# PR9021.net
KiCad netlist of a schematic drawn in EAGLE
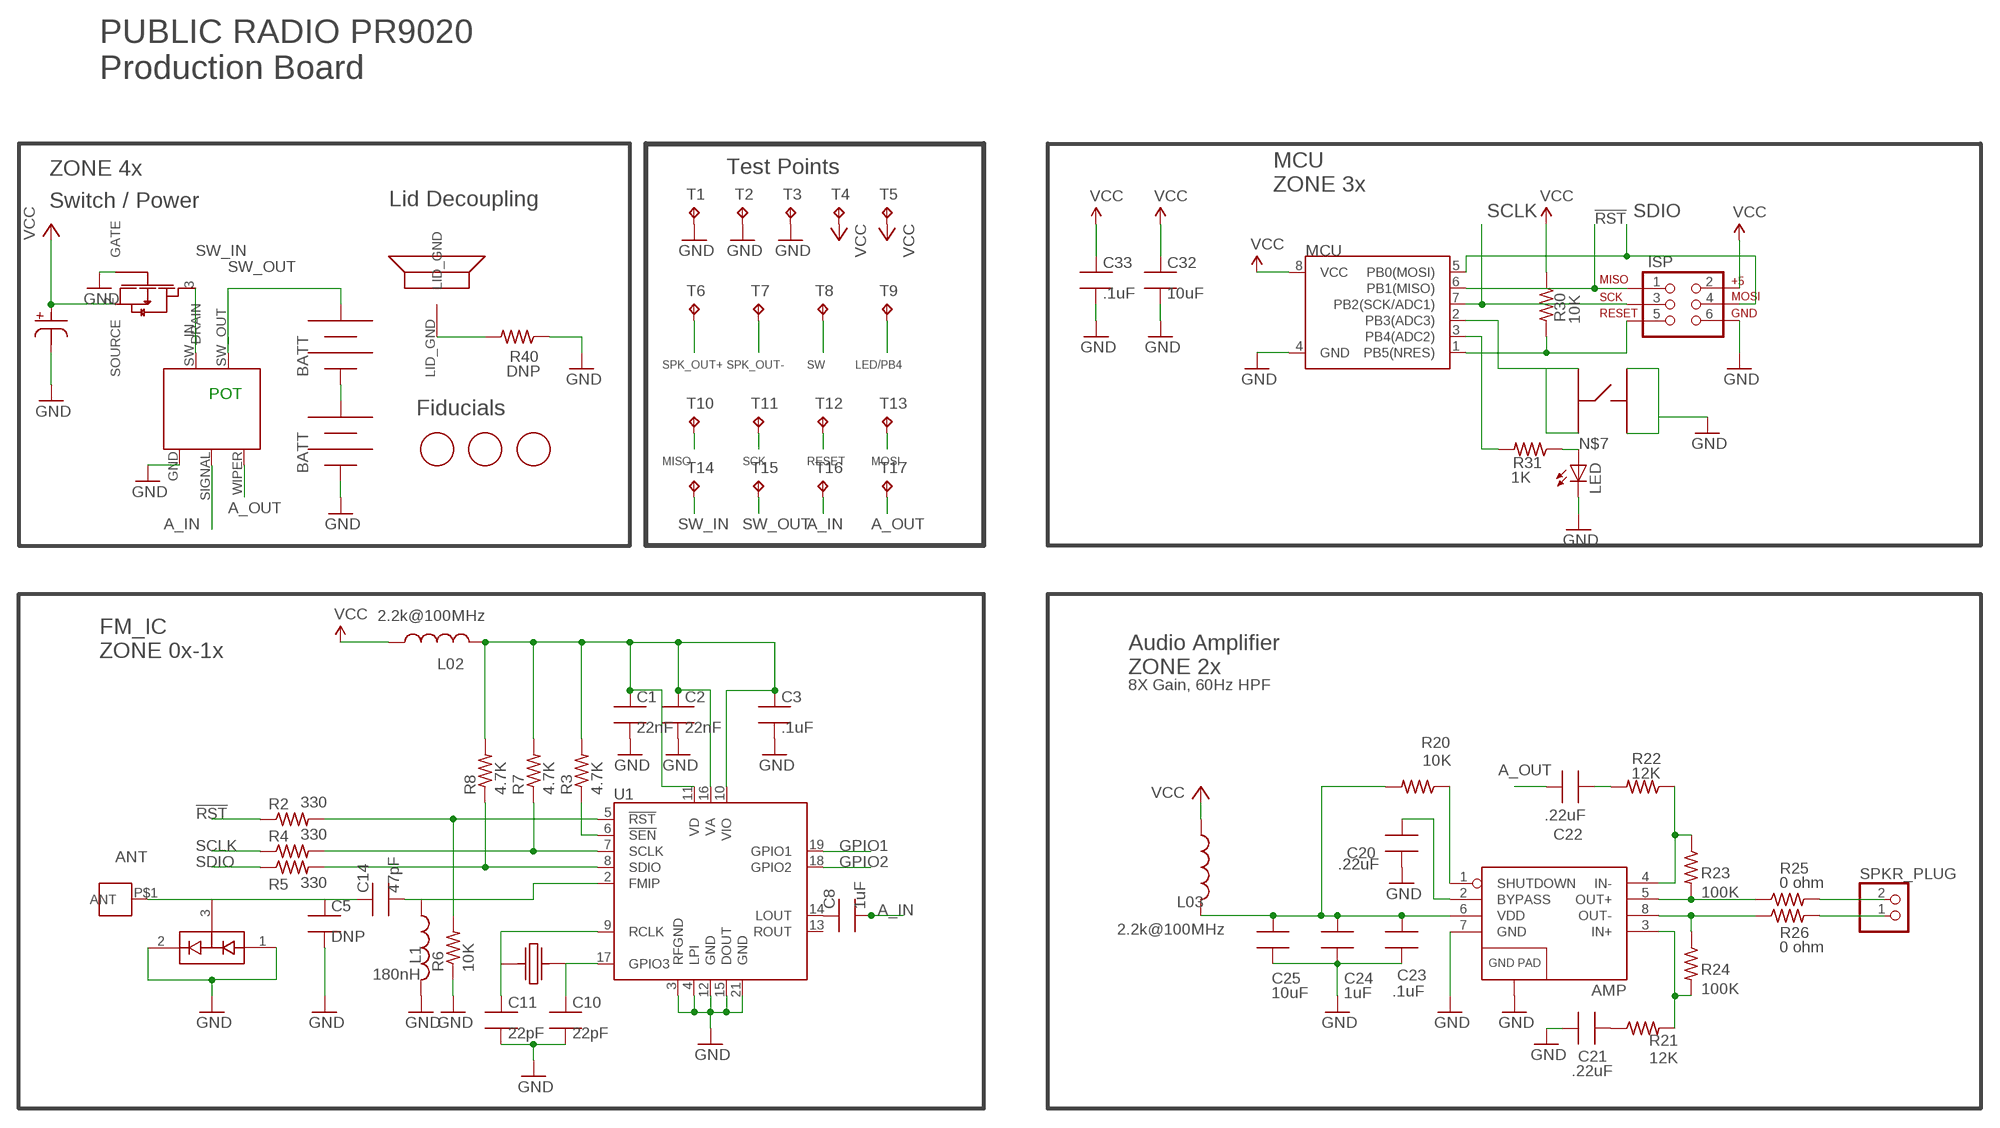
[diagram p0: schematic, sheet 1]

(export (version "E")
  (design (tool "Eeschema 10.0.6"))
  (components
    (comp (ref "AMP")
      (value "TPA6203A1")
      (footprint "eagle-import:8-MSOP")
      (libsource (lib "eagle-import") (part "TPA6203A1"))
    )
    (comp (ref "ANT_MOUNT")
      (value "DNP")
      (footprint "eagle-import:M3_BOLT_HOLE")
      (libsource (lib "eagle-import") (part "M3_SCREW_POST"))
    )
    (comp (ref "C1")
      (value "22nF")
      (footprint "eagle-import:0603_CPL")
      (fields
        (field (name "MFG_PN") "CL10B223KB8NNNC")
        (field (name "TOL") "10%")
        (field (name "VOLTAGE") "16V")
      )
      (libsource (lib "eagle-import") (part "C_SMT_0603_CPL"))
    )
    (comp (ref "C2")
      (value "22nF")
      (footprint "eagle-import:0603_CPL")
      (fields
        (field (name "MFG_PN") "CL10B223KB8NNNC")
        (field (name "TOL") "10%")
        (field (name "VOLTAGE") "16V")
      )
      (libsource (lib "eagle-import") (part "C_SMT_0603_CPL"))
    )
    (comp (ref "C3")
      (value ".1uF")
      (footprint "eagle-import:0603_CPL")
      (fields
        (field (name "MFG_PN") "CL10B104KB8SFNC")
        (field (name "TOL") "10%")
        (field (name "VOLTAGE") "16V")
      )
      (libsource (lib "eagle-import") (part "C_SMT_0603_CPL"))
    )
    (comp (ref "C5")
      (value "DNP")
      (footprint "eagle-import:0603_CPL")
      (fields (field (name "MFG_PN") "DNP") (field (name "TOL") "2%") (field (name "VOLTAGE") "50V"))
      (libsource (lib "eagle-import") (part "C_SMT_0603_CPL"))
    )
    (comp (ref "C8")
      (value "1uF")
      (footprint "eagle-import:0603_CPL")
      (fields
        (field (name "MFG_PN") "CL10B105KP8NNNC")
        (field (name "TOL") "10%")
        (field (name "VOLTAGE") "10V")
      )
      (libsource (lib "eagle-import") (part "C_SMT_0603_CPL"))
    )
    (comp (ref "C10")
      (value "22pF")
      (footprint "eagle-import:0603_CPL")
      (fields
        (field (name "MFG_PN") "C1608C0G1H220J080AA")
        (field (name "TOL") "5%")
        (field (name "VOLTAGE") "50V")
      )
      (libsource (lib "eagle-import") (part "C_SMT_0603_CPL"))
    )
    (comp (ref "C11")
      (value "22pF")
      (footprint "eagle-import:0603_CPL")
      (fields
        (field (name "MFG_PN") "C1608C0G1H220J080AA")
        (field (name "TOL") "5%")
        (field (name "VOLTAGE") "50V")
      )
      (libsource (lib "eagle-import") (part "C_SMT_0603_CPL"))
    )
    (comp (ref "C14")
      (value "47pF")
      (footprint "eagle-import:0603_CPL")
      (fields
        (field (name "MFG_PN") "CL10C470JB8NCNC")
        (field (name "TOL") "5%")
        (field (name "VOLTAGE") "50V")
      )
      (libsource (lib "eagle-import") (part "C_SMT_0603_CPL"))
    )
    (comp (ref "C20")
      (value ".22uF")
      (footprint "eagle-import:0603_CPL")
      (fields
        (field (name "MFG_PN") "C1608X7R1C224K080AC")
        (field (name "TOL") "10%")
        (field (name "VOLTAGE") "16V")
      )
      (libsource (lib "eagle-import") (part "C_SMT_0603_CPL"))
    )
    (comp (ref "C21")
      (value ".22uF")
      (footprint "eagle-import:0603_CPL")
      (fields
        (field (name "MFG_PN") "C1608X7R1C224K080AC")
        (field (name "TOL") "10%")
        (field (name "VOLTAGE") "16V")
      )
      (libsource (lib "eagle-import") (part "C_SMT_0603_CPL"))
    )
    (comp (ref "C22")
      (value ".22uF")
      (footprint "eagle-import:0603_CPL")
      (fields
        (field (name "MFG_PN") "C1608X7R1C224K080AC")
        (field (name "TOL") "10%")
        (field (name "VOLTAGE") "16V")
      )
      (libsource (lib "eagle-import") (part "C_SMT_0603_CPL"))
    )
    (comp (ref "C23")
      (value ".1uF")
      (footprint "eagle-import:0603_CPL")
      (fields
        (field (name "MFG_PN") "CL10B104KB8SFNC")
        (field (name "TOL") "10%")
        (field (name "VOLTAGE") "16V")
      )
      (libsource (lib "eagle-import") (part "C_SMT_0603_CPL"))
    )
    (comp (ref "C24")
      (value "1uF")
      (footprint "eagle-import:0603_CPL")
      (fields
        (field (name "MFG_PN") "CL10B105KP8NNNC")
        (field (name "TOL") "10%")
        (field (name "VOLTAGE") "10V")
      )
      (libsource (lib "eagle-import") (part "C_SMT_0603_CPL"))
    )
    (comp (ref "C25")
      (value "10uF")
      (footprint "eagle-import:0603_CPL")
      (fields
        (field (name "MFG_PN") "CL10A106MQ8NNNC")
        (field (name "TOL") "20%")
        (field (name "VOLTAGE") "6.3V")
      )
      (libsource (lib "eagle-import") (part "C_SMT_0603_CPL"))
    )
    (comp (ref "C32")
      (value "10uF")
      (footprint "eagle-import:0603_CPL")
      (fields
        (field (name "MFG_PN") "CL10A106MQ8NNNC")
        (field (name "TOL") "20%")
        (field (name "VOLTAGE") "6.3V")
      )
      (libsource (lib "eagle-import") (part "C_SMT_0603_CPL"))
    )
    (comp (ref "C33")
      (value ".1uF")
      (footprint "eagle-import:0603_CPL")
      (fields
        (field (name "MFG_PN") "CL10B104KB8SFNC")
        (field (name "TOL") "10%")
        (field (name "VOLTAGE") "16V")
      )
      (libsource (lib "eagle-import") (part "C_SMT_0603_CPL"))
    )
    (comp (ref "C40")
      (value "220uF")
      (footprint "eagle-import:NICHICON_UD_63")
      (fields (field (name "TOL") "20%") (field (name "VOLTAGE") "16V"))
      (libsource (lib "eagle-import") (part "NICHICON_SERIESUD"))
    )
    (comp (ref "D1")
      (value "BAV99")
      (footprint "eagle-import:SOT23_CPL")
      (fields (field (name "MFG_PN") "BAV99,215"))
      (libsource (lib "eagle-import") (part "BAV99"))
    )
    (comp (ref "FET1")
      (value "AO3435")
      (footprint "eagle-import:SOT23_CPL")
      (fields (field (name "MFG_PN") "AO3435"))
      (libsource (lib "eagle-import") (part "AO3435"))
    )
    (comp (ref "ISP")
      (value "AVR_SPI_PRG_6NS")
      (footprint "eagle-import:2X3-NS")
      (libsource (lib "eagle-import") (part "AVR_SPI_PRG_6NS"))
    )
    (comp (ref "JP5")
      (value "BK-92_MPD_AA_BATT_CLIP")
      (footprint "eagle-import:BK92_AA_BATT")
      (fields (field (name "MFG_PN") "2 of BK92 - supplied by CL Labs"))
      (libsource (lib "eagle-import") (part "BK-92_MPD_AA_BATT_CLIP"))
    )
    (comp (ref "JP6")
      (value "BK-92_MPD_AA_BATT_CLIP")
      (footprint "eagle-import:BK92_AA_BATT")
      (fields (field (name "MFG_PN") "2 of BK92 - supplied by CL Labs"))
      (libsource (lib "eagle-import") (part "BK-92_MPD_AA_BATT_CLIP"))
    )
    (comp (ref "L1")
      (value "180nH")
      (footprint "eagle-import:0805_ADAFRUIT")
      (fields
        (field (name "CURRENT") "400mA")
        (field (name "DCR") "640m")
        (field (name "MFG_PN") "AISC-0805-R18J-T")
        (field (name "TOL") "5%")
      )
      (libsource (lib "eagle-import") (part "L_SMT_0805_ADAFRUIT"))
    )
    (comp (ref "L02")
      (value "2.2k@100MHz")
      (footprint "eagle-import:0603_CPL")
      (fields
        (field (name "CURRENT") "150mA")
        (field (name "DCR") "2.3")
        (field (name "MFG_PN") "HZ0603A222R-10")
      )
      (libsource (lib "eagle-import") (part "L_SMT_0603_CPL"))
    )
    (comp (ref "L03")
      (value "2.2k@100MHz")
      (footprint "eagle-import:0603_CPL")
      (fields
        (field (name "CURRENT") "150mA")
        (field (name "DCR") "2.3")
        (field (name "MFG_PN") "HZ0603A222R-10")
      )
      (libsource (lib "eagle-import") (part "L_SMT_0603_CPL"))
    )
    (comp (ref "LED")
      (value "LEDCHIPLED_0805")
      (footprint "eagle-import:CHIPLED_0805")
      (libsource (lib "eagle-import") (part "LEDCHIPLED_0805"))
    )
    (comp (ref "MARK1")
      (value "FIDUCIAL")
      (footprint "eagle-import:FIDUCIAL_1MM")
      (libsource (lib "eagle-import") (part "FIDUCIAL"))
    )
    (comp (ref "MARK2")
      (value "FIDUCIAL")
      (footprint "eagle-import:FIDUCIAL_1MM")
      (libsource (lib "eagle-import") (part "FIDUCIAL"))
    )
    (comp (ref "MARK3")
      (value "FIDUCIAL")
      (footprint "eagle-import:FIDUCIAL_1MM")
      (libsource (lib "eagle-import") (part "FIDUCIAL"))
    )
    (comp (ref "MCU")
      (value "ATTINY45TINY45-20-SMT")
      (footprint "eagle-import:8-SOIC")
      (libsource (lib "eagle-import") (part "ATTINY45TINY45-20-SMT"))
    )
    (comp (ref "R1")
      (value "RV170SF_TAIWANA_POT_SW")
      (footprint "eagle-import:RV170SF_SW_POT")
      (fields (field (name "MFG_PN") "RV170SF-43-20F-A10K - supplied by CL Labs"))
      (libsource (lib "eagle-import") (part "RV170SF_TAIWANA_POT_SW"))
    )
    (comp (ref "R2")
      (value "330")
      (footprint "eagle-import:0603_CPL")
      (fields (field (name "MFG_PN") "MCR03ERTJ331") (field (name "POWER") "1/10W") (field (name "TOL") "5%"))
      (libsource (lib "eagle-import") (part "R_SMT_R0603_CPL"))
    )
    (comp (ref "R3")
      (value "4.7K")
      (footprint "eagle-import:0603_CPL")
      (fields
        (field (name "MFG_PN") "ERJ-3EKF4701V")
        (field (name "POWER") "1/10W")
        (field (name "TOL") "1%")
      )
      (libsource (lib "eagle-import") (part "R_SMT_R0603_CPL"))
    )
    (comp (ref "R4")
      (value "330")
      (footprint "eagle-import:0603_CPL")
      (fields (field (name "MFG_PN") "MCR03ERTJ331") (field (name "POWER") "1/10W") (field (name "TOL") "5%"))
      (libsource (lib "eagle-import") (part "R_SMT_R0603_CPL"))
    )
    (comp (ref "R5")
      (value "330")
      (footprint "eagle-import:0603_CPL")
      (fields (field (name "MFG_PN") "MCR03ERTJ331") (field (name "POWER") "1/10W") (field (name "TOL") "5%"))
      (libsource (lib "eagle-import") (part "R_SMT_R0603_CPL"))
    )
    (comp (ref "R6")
      (value "10K")
      (footprint "eagle-import:0603_CPL")
      (fields
        (field (name "MFG_PN") "ERJ-3GEYJ103V")
        (field (name "POWER") "1/10W")
        (field (name "TOL") "5%")
      )
      (libsource (lib "eagle-import") (part "R_SMT_R0603_CPL"))
    )
    (comp (ref "R7")
      (value "4.7K")
      (footprint "eagle-import:0603_CPL")
      (fields
        (field (name "MFG_PN") "ERJ-3EKF4701V")
        (field (name "POWER") "1/10W")
        (field (name "TOL") "1%")
      )
      (libsource (lib "eagle-import") (part "R_SMT_R0603_CPL"))
    )
    (comp (ref "R8")
      (value "4.7K")
      (footprint "eagle-import:0603_CPL")
      (fields
        (field (name "MFG_PN") "ERJ-3EKF4701V")
        (field (name "POWER") "1/10W")
        (field (name "TOL") "1%")
      )
      (libsource (lib "eagle-import") (part "R_SMT_R0603_CPL"))
    )
    (comp (ref "R20")
      (value "10K")
      (footprint "eagle-import:0603_CPL")
      (fields
        (field (name "MFG_PN") "ERJ-3GEYJ103V")
        (field (name "POWER") "1/10W")
        (field (name "TOL") "5%")
      )
      (libsource (lib "eagle-import") (part "R_SMT_R0603_CPL"))
    )
    (comp (ref "R21")
      (value "12K")
      (footprint "eagle-import:0603_CPL")
      (fields
        (field (name "MFG_PN") "RC0603FR-0712KL")
        (field (name "POWER") "1/10W")
        (field (name "TOL") "1%")
      )
      (libsource (lib "eagle-import") (part "R_SMT_R0603_CPL"))
    )
    (comp (ref "R22")
      (value "12K")
      (footprint "eagle-import:0603_CPL")
      (fields
        (field (name "MFG_PN") "RC0603FR-0712KL")
        (field (name "POWER") "1/10W")
        (field (name "TOL") "1%")
      )
      (libsource (lib "eagle-import") (part "R_SMT_R0603_CPL"))
    )
    (comp (ref "R23")
      (value "100K")
      (footprint "eagle-import:0603_CPL")
      (fields
        (field (name "MFG_PN") "ERJ-3EKF1003V")
        (field (name "POWER") "1/10W")
        (field (name "TOL") "1%")
      )
      (libsource (lib "eagle-import") (part "R_SMT_R0603_CPL"))
    )
    (comp (ref "R24")
      (value "100K")
      (footprint "eagle-import:0603_CPL")
      (fields
        (field (name "MFG_PN") "ERJ-3EKF1003V")
        (field (name "POWER") "1/10W")
        (field (name "TOL") "1%")
      )
      (libsource (lib "eagle-import") (part "R_SMT_R0603_CPL"))
    )
    (comp (ref "R25")
      (value "0 ohm")
      (footprint "eagle-import:0805_ADAFRUIT")
      (fields (field (name "MFG_PN") "ERJ-6GEY0R00V"))
      (libsource (lib "eagle-import") (part "R_SMT_0805_ADAFRUIT"))
    )
    (comp (ref "R26")
      (value "0 ohm")
      (footprint "eagle-import:0805_ADAFRUIT")
      (fields (field (name "MFG_PN") "ERJ-6GEY0R00V"))
      (libsource (lib "eagle-import") (part "R_SMT_0805_ADAFRUIT"))
    )
    (comp (ref "R30")
      (value "10K")
      (footprint "eagle-import:0603_CPL")
      (fields
        (field (name "MFG_PN") "ERJ-3GEYJ103V")
        (field (name "POWER") "1/10W")
        (field (name "TOL") "5%")
      )
      (libsource (lib "eagle-import") (part "R_SMT_R0603_CPL"))
    )
    (comp (ref "R31")
      (value "1K")
      (footprint "eagle-import:0603_CPL")
      (fields
        (field (name "MFG_PN") "ERJ-3EKF1001V")
        (field (name "POWER") "1/10W")
        (field (name "TOL") "1%")
      )
      (libsource (lib "eagle-import") (part "R_SMT_R0603_CPL"))
    )
    (comp (ref "R40")
      (value "DNP")
      (footprint "eagle-import:0603_CPL")
      (fields (field (name "MFG_PN") "ERJ-3GEY0R00V"))
      (libsource (lib "eagle-import") (part "R_SMT_R0603_CPL"))
    )
    (comp (ref "SPKR_PLACE")
      (value "DNP")
      (footprint "eagle-import:PR2023_SPKR_PLACE")
      (libsource (lib "eagle-import") (part "PR2023_SPKR"))
    )
    (comp (ref "SPKR_PLUG")
      (value "JST_2PIN-SMT-RA")
      (footprint "eagle-import:JST-B2B-PH-SM4-TB")
      (libsource (lib "eagle-import") (part "JST_2PIN-SMT-RA"))
    )
    (comp (ref "SW1")
      (value "C&K_PTS645")
      (footprint "eagle-import:C&K_PTS645_SMT")
      (libsource (lib "eagle-import") (part "C&K_PTS645"))
    )
    (comp (ref "T1")
      (value "TPTP20R")
      (footprint "eagle-import:TP20R")
      (libsource (lib "eagle-import") (part "TPTP20R"))
    )
    (comp (ref "T2")
      (value "TPTP20R")
      (footprint "eagle-import:TP20R")
      (libsource (lib "eagle-import") (part "TPTP20R"))
    )
    (comp (ref "T3")
      (value "TPTP20R")
      (footprint "eagle-import:TP20R")
      (libsource (lib "eagle-import") (part "TPTP20R"))
    )
    (comp (ref "T4")
      (value "TPTP20R")
      (footprint "eagle-import:TP20R")
      (libsource (lib "eagle-import") (part "TPTP20R"))
    )
    (comp (ref "T5")
      (value "TPTP20R")
      (footprint "eagle-import:TP20R")
      (libsource (lib "eagle-import") (part "TPTP20R"))
    )
    (comp (ref "T6")
      (value "TPTP20R")
      (footprint "eagle-import:TP20R")
      (libsource (lib "eagle-import") (part "TPTP20R"))
    )
    (comp (ref "T7")
      (value "TPTP20R")
      (footprint "eagle-import:TP20R")
      (libsource (lib "eagle-import") (part "TPTP20R"))
    )
    (comp (ref "T8")
      (value "TPTP20R")
      (footprint "eagle-import:TP20R")
      (libsource (lib "eagle-import") (part "TPTP20R"))
    )
    (comp (ref "T9")
      (value "TPTP20R")
      (footprint "eagle-import:TP20R")
      (libsource (lib "eagle-import") (part "TPTP20R"))
    )
    (comp (ref "T10")
      (value "TPTP20R")
      (footprint "eagle-import:TP20R")
      (libsource (lib "eagle-import") (part "TPTP20R"))
    )
    (comp (ref "T11")
      (value "TPTP20R")
      (footprint "eagle-import:TP20R")
      (libsource (lib "eagle-import") (part "TPTP20R"))
    )
    (comp (ref "T12")
      (value "TPTP20R")
      (footprint "eagle-import:TP20R")
      (libsource (lib "eagle-import") (part "TPTP20R"))
    )
    (comp (ref "T13")
      (value "TPTP20R")
      (footprint "eagle-import:TP20R")
      (libsource (lib "eagle-import") (part "TPTP20R"))
    )
    (comp (ref "T14")
      (value "TPTP20R")
      (footprint "eagle-import:TP20R")
      (libsource (lib "eagle-import") (part "TPTP20R"))
    )
    (comp (ref "T15")
      (value "TPTP20R")
      (footprint "eagle-import:TP20R")
      (libsource (lib "eagle-import") (part "TPTP20R"))
    )
    (comp (ref "T16")
      (value "TPTP20R")
      (footprint "eagle-import:TP20R")
      (libsource (lib "eagle-import") (part "TPTP20R"))
    )
    (comp (ref "T17")
      (value "TPTP20R")
      (footprint "eagle-import:TP20R")
      (libsource (lib "eagle-import") (part "TPTP20R"))
    )
    (comp (ref "U1")
      (value "SI4702-C19-GMR")
      (footprint "eagle-import:SI470X_20_QFN")
      (fields (field (name "MFG_PN") "Si4702 C19 GM - supplied by CL Labs"))
      (libsource (lib "eagle-import") (part "SI4702-C19-GMR"))
    )
    (comp (ref "X1")
      (value "ABS25XTAL")
      (footprint "eagle-import:4-SOJ")
      (libsource (lib "eagle-import") (part "ABS25XTAL"))
    )
  )
  (nets
    (net (code "1") (name "/ANT") (class "Default")
      (node (ref "ANT_MOUNT") (pin "P$1") (pinfunction "ANT_P$1") (pintype "bidirectional"))
      (node (ref "C14") (pin "1") (pinfunction "1_1") (pintype "passive"))
      (node (ref "C5") (pin "1") (pinfunction "1_1") (pintype "passive"))
      (node (ref "D1") (pin "3") (pinfunction "COM_3") (pintype "bidirectional"))
    )
    (net (code "2") (name "/A_IN") (class "Default")
      (node (ref "C8") (pin "2") (pinfunction "2_2") (pintype "passive"))
      (node (ref "R1") (pin "SIGNAL") (pinfunction "SIGNAL_SIGNAL") (pintype "bidirectional"))
      (node (ref "T16") (pin "TP") (pinfunction "TP_TP") (pintype "input"))
    )
    (net (code "3") (name "/A_OUT") (class "Default")
      (node (ref "C22") (pin "2") (pinfunction "2_2") (pintype "passive"))
      (node (ref "R1") (pin "WIPER") (pinfunction "WIPER_WIPER") (pintype "bidirectional"))
      (node (ref "T17") (pin "TP") (pinfunction "TP_TP") (pintype "input"))
    )
    (net (code "4") (name "/GPIO1") (class "Default")
      (node (ref "U1") (pin "19") (pinfunction "GPIO1_19") (pintype "bidirectional"))
    )
    (net (code "5") (name "/GPIO2") (class "Default")
      (node (ref "U1") (pin "18") (pinfunction "GPIO2_18") (pintype "bidirectional"))
    )
    (net (code "6") (name "/LED{slash}PB4") (class "Default")
      (node (ref "MCU") (pin "3") (pinfunction "PB4(ADC2)_3") (pintype "bidirectional"))
      (node (ref "R31") (pin "2") (pinfunction "2_2") (pintype "passive"))
      (node (ref "T9") (pin "TP") (pinfunction "TP_TP") (pintype "input"))
    )
    (net (code "7") (name "/N$7") (class "Default")
      (node (ref "LED") (pin "A") (pinfunction "A_A") (pintype "passive"))
      (node (ref "R31") (pin "1") (pinfunction "1_1") (pintype "passive"))
    )
    (net (code "8") (name "/RESET") (class "Default")
      (node (ref "ISP") (pin "5") (pinfunction "5_5") (pintype "passive"))
      (node (ref "MCU") (pin "1") (pinfunction "PB5(NRES)_1") (pintype "bidirectional"))
      (node (ref "R30") (pin "2") (pinfunction "2_2") (pintype "passive"))
      (node (ref "T12") (pin "TP") (pinfunction "TP_TP") (pintype "input"))
    )
    (net (code "9") (name "/SCLK") (class "Default")
      (node (ref "ISP") (pin "3") (pinfunction "3_3") (pintype "passive"))
      (node (ref "MCU") (pin "7") (pinfunction "PB2(SCK/ADC1)_7") (pintype "bidirectional"))
      (node (ref "R4") (pin "1") (pinfunction "1_1") (pintype "passive"))
      (node (ref "T11") (pin "TP") (pinfunction "TP_TP") (pintype "input"))
    )
    (net (code "10") (name "/SDIO") (class "Default")
      (node (ref "ISP") (pin "4") (pinfunction "4_4") (pintype "passive"))
      (node (ref "MCU") (pin "5") (pinfunction "PB0(MOSI)_5") (pintype "bidirectional"))
      (node (ref "R5") (pin "1") (pinfunction "1_1") (pintype "passive"))
      (node (ref "T13") (pin "TP") (pinfunction "TP_TP") (pintype "input"))
    )
    (net (code "11") (name "/SPK_OUT+") (class "Default")
      (node (ref "R25") (pin "2") (pinfunction "2_2") (pintype "passive"))
      (node (ref "SPKR_PLUG") (pin "2") (pinfunction "1_2") (pintype "passive"))
      (node (ref "T6") (pin "TP") (pinfunction "TP_TP") (pintype "input"))
    )
    (net (code "12") (name "/SPK_OUT-") (class "Default")
      (node (ref "R26") (pin "2") (pinfunction "2_2") (pintype "passive"))
      (node (ref "SPKR_PLUG") (pin "1") (pinfunction "2_1") (pintype "passive"))
      (node (ref "T7") (pin "TP") (pinfunction "TP_TP") (pintype "input"))
    )
    (net (code "13") (name "/SW") (class "Default")
      (node (ref "MCU") (pin "2") (pinfunction "PB3(ADC3)_2") (pintype "bidirectional"))
      (node (ref "SW1") (pin "P$3") (pinfunction "P$3_P$3") (pintype "bidirectional"))
      (node (ref "SW1") (pin "P$4") (pinfunction "P$4_P$4") (pintype "bidirectional"))
      (node (ref "T8") (pin "TP") (pinfunction "TP_TP") (pintype "input"))
    )
    (net (code "14") (name "/SW_IN") (class "Default")
      (node (ref "FET1") (pin "3") (pinfunction "DRAIN_3") (pintype "bidirectional"))
      (node (ref "R1") (pin "SW_IN") (pinfunction "SW_IN_SW_IN") (pintype "bidirectional"))
      (node (ref "T14") (pin "TP") (pinfunction "TP_TP") (pintype "input"))
    )
    (net (code "15") (name "/SW_OUT") (class "Default")
      (node (ref "JP5") (pin "POS") (pinfunction "POS_POS") (pintype "bidirectional"))
      (node (ref "JP5") (pin "POS@2") (pinfunction "POS_POS@2") (pintype "bidirectional"))
      (node (ref "R1") (pin "SW_OUT") (pinfunction "SW_OUT_SW_OUT") (pintype "bidirectional"))
      (node (ref "T15") (pin "TP") (pinfunction "TP_TP") (pintype "input"))
    )
    (net (code "16") (name "/~{RST}") (class "Default")
      (node (ref "ISP") (pin "1") (pinfunction "1_1") (pintype "passive"))
      (node (ref "MCU") (pin "6") (pinfunction "PB1(MISO)_6") (pintype "bidirectional"))
      (node (ref "R2") (pin "1") (pinfunction "1_1") (pintype "passive"))
      (node (ref "T10") (pin "TP") (pinfunction "TP_TP") (pintype "input"))
    )
    (net (code "17") (name "GND") (class "Default")
      (node (ref "AMP") (pin "7") (pinfunction "GND_7") (pintype "power_in"))
      (node (ref "AMP") (pin "9") (pinfunction "GND_9") (pintype "power_in"))
      (node (ref "C1") (pin "2") (pinfunction "2_2") (pintype "passive"))
      (node (ref "C10") (pin "2") (pinfunction "2_2") (pintype "passive"))
      (node (ref "C11") (pin "2") (pinfunction "2_2") (pintype "passive"))
      (node (ref "C2") (pin "2") (pinfunction "2_2") (pintype "passive"))
      (node (ref "C20") (pin "1") (pinfunction "1_1") (pintype "passive"))
      (node (ref "C21") (pin "1") (pinfunction "1_1") (pintype "passive"))
      (node (ref "C23") (pin "2") (pinfunction "2_2") (pintype "passive"))
      (node (ref "C24") (pin "2") (pinfunction "2_2") (pintype "passive"))
      (node (ref "C25") (pin "2") (pinfunction "2_2") (pintype "passive"))
      (node (ref "C3") (pin "2") (pinfunction "2_2") (pintype "passive"))
      (node (ref "C32") (pin "2") (pinfunction "2_2") (pintype "passive"))
      (node (ref "C33") (pin "2") (pinfunction "2_2") (pintype "passive"))
      (node (ref "C40") (pin "P$2") (pinfunction "P$2_P$2") (pintype "bidirectional"))
      (node (ref "C5") (pin "2") (pinfunction "2_2") (pintype "passive"))
      (node (ref "D1") (pin "1") (pinfunction "A1_1") (pintype "bidirectional"))
      (node (ref "D1") (pin "2") (pinfunction "C2_2") (pintype "bidirectional"))
      (node (ref "FET1") (pin "1") (pinfunction "GATE_1") (pintype "bidirectional"))
      (node (ref "ISP") (pin "6") (pinfunction "6_6") (pintype "passive"))
      (node (ref "JP6") (pin "NEG") (pinfunction "NEG_NEG") (pintype "bidirectional"))
      (node (ref "JP6") (pin "NEG@2") (pinfunction "NEG_NEG@2") (pintype "bidirectional"))
      (node (ref "L1") (pin "2") (pinfunction "2_2") (pintype "passive"))
      (node (ref "LED") (pin "C") (pinfunction "C_C") (pintype "passive"))
      (node (ref "MCU") (pin "4") (pinfunction "GND_4") (pintype "bidirectional"))
      (node (ref "R1") (pin "GND") (pinfunction "GND_GND") (pintype "bidirectional"))
      (node (ref "R40") (pin "1") (pinfunction "1_1") (pintype "passive"))
      (node (ref "R6") (pin "1") (pinfunction "1_1") (pintype "passive"))
      (node (ref "SW1") (pin "P$1") (pinfunction "P$1_P$1") (pintype "bidirectional"))
      (node (ref "SW1") (pin "P$2") (pinfunction "P$2_P$2") (pintype "bidirectional"))
      (node (ref "T1") (pin "TP") (pinfunction "TP_TP") (pintype "input"))
      (node (ref "T2") (pin "TP") (pinfunction "TP_TP") (pintype "input"))
      (node (ref "T3") (pin "TP") (pinfunction "TP_TP") (pintype "input"))
      (node (ref "U1") (pin "12") (pinfunction "GND_12") (pintype "bidirectional"))
      (node (ref "U1") (pin "15") (pinfunction "DOUT_15") (pintype "bidirectional"))
      (node (ref "U1") (pin "21") (pinfunction "GND_21") (pintype "bidirectional"))
      (node (ref "U1") (pin "3") (pinfunction "RFGND_3") (pintype "bidirectional"))
      (node (ref "U1") (pin "4") (pinfunction "LPI_4") (pintype "bidirectional"))
    )
    (net (code "18") (name "Net-(AMP-BYPASS)") (class "Default")
      (node (ref "AMP") (pin "2") (pinfunction "BYPASS_2") (pintype "bidirectional"))
      (node (ref "C20") (pin "2") (pinfunction "2_2") (pintype "passive"))
    )
    (net (code "19") (name "Net-(AMP-IN+)") (class "Default")
      (node (ref "AMP") (pin "3") (pinfunction "IN+_3") (pintype "bidirectional"))
      (node (ref "R21") (pin "2") (pinfunction "2_2") (pintype "passive"))
      (node (ref "R24") (pin "2") (pinfunction "2_2") (pintype "passive"))
    )
    (net (code "20") (name "Net-(AMP-IN-)") (class "Default")
      (node (ref "AMP") (pin "4") (pinfunction "IN-_4") (pintype "bidirectional"))
      (node (ref "R22") (pin "1") (pinfunction "1_1") (pintype "passive"))
      (node (ref "R23") (pin "1") (pinfunction "1_1") (pintype "passive"))
    )
    (net (code "21") (name "Net-(AMP-OUT+)") (class "Default")
      (node (ref "AMP") (pin "5") (pinfunction "OUT+_5") (pintype "bidirectional"))
      (node (ref "R23") (pin "2") (pinfunction "2_2") (pintype "passive"))
      (node (ref "R25") (pin "1") (pinfunction "1_1") (pintype "passive"))
    )
    (net (code "22") (name "Net-(AMP-OUT-)") (class "Default")
      (node (ref "AMP") (pin "8") (pinfunction "OUT-_8") (pintype "bidirectional"))
      (node (ref "R24") (pin "1") (pinfunction "1_1") (pintype "passive"))
      (node (ref "R26") (pin "1") (pinfunction "1_1") (pintype "passive"))
    )
    (net (code "23") (name "Net-(AMP-SHUTDOWN)") (class "Default")
      (node (ref "AMP") (pin "1") (pinfunction "SHUTDOWN_1") (pintype "input"))
      (node (ref "R20") (pin "1") (pinfunction "1_1") (pintype "passive"))
    )
    (net (code "24") (name "Net-(AMP-VDD)") (class "Default")
      (node (ref "AMP") (pin "6") (pinfunction "VDD_6") (pintype "power_in"))
      (node (ref "C23") (pin "1") (pinfunction "1_1") (pintype "passive"))
      (node (ref "C24") (pin "1") (pinfunction "1_1") (pintype "passive"))
      (node (ref "C25") (pin "1") (pinfunction "1_1") (pintype "passive"))
      (node (ref "L03") (pin "2") (pinfunction "2_2") (pintype "passive"))
      (node (ref "R20") (pin "2") (pinfunction "2_2") (pintype "passive"))
    )
    (net (code "25") (name "Net-(C21-Pad2)") (class "Default")
      (node (ref "C21") (pin "2") (pinfunction "2_2") (pintype "passive"))
      (node (ref "R21") (pin "1") (pinfunction "1_1") (pintype "passive"))
    )
    (net (code "26") (name "Net-(C22-Pad1)") (class "Default")
      (node (ref "C22") (pin "1") (pinfunction "1_1") (pintype "passive"))
      (node (ref "R22") (pin "2") (pinfunction "2_2") (pintype "passive"))
    )
    (net (code "27") (name "Net-(JP5-NEG-PadNEG@2)") (class "Default")
      (node (ref "JP5") (pin "NEG") (pinfunction "NEG_NEG") (pintype "bidirectional"))
      (node (ref "JP5") (pin "NEG@2") (pinfunction "NEG_NEG@2") (pintype "bidirectional"))
      (node (ref "JP6") (pin "POS") (pinfunction "POS_POS") (pintype "bidirectional"))
      (node (ref "JP6") (pin "POS@2") (pinfunction "POS_POS@2") (pintype "bidirectional"))
    )
    (net (code "28") (name "Net-(R40-Pad2)") (class "Default")
      (node (ref "R40") (pin "2") (pinfunction "2_2") (pintype "passive"))
      (node (ref "SPKR_PLACE") (pin "LID_GND") (pinfunction "LID_GND_LID_GND") (pintype "bidirectional"))
    )
    (net (code "29") (name "Net-(U1-FMIP)") (class "Default")
      (node (ref "C14") (pin "2") (pinfunction "2_2") (pintype "passive"))
      (node (ref "L1") (pin "1") (pinfunction "1_1") (pintype "passive"))
      (node (ref "U1") (pin "2") (pinfunction "FMIP_2") (pintype "bidirectional"))
    )
    (net (code "30") (name "Net-(U1-GPIO3)") (class "Default")
      (node (ref "C10") (pin "1") (pinfunction "1_1") (pintype "passive"))
      (node (ref "U1") (pin "17") (pinfunction "GPIO3_17") (pintype "bidirectional"))
      (node (ref "X1") (pin "P$4") (pinfunction "P$4_P$4") (pintype "bidirectional"))
    )
    (net (code "31") (name "Net-(U1-LOUT)") (class "Default")
      (node (ref "C8") (pin "1") (pinfunction "1_1") (pintype "passive"))
      (node (ref "U1") (pin "14") (pinfunction "LOUT_14") (pintype "bidirectional"))
    )
    (net (code "32") (name "Net-(U1-RCLK)") (class "Default")
      (node (ref "C11") (pin "1") (pinfunction "1_1") (pintype "passive"))
      (node (ref "U1") (pin "9") (pinfunction "RCLK_9") (pintype "bidirectional"))
      (node (ref "X1") (pin "P$1") (pinfunction "P$1_P$1") (pintype "bidirectional"))
    )
    (net (code "33") (name "Net-(U1-SCLK)") (class "Default")
      (node (ref "R4") (pin "2") (pinfunction "2_2") (pintype "passive"))
      (node (ref "R7") (pin "1") (pinfunction "1_1") (pintype "passive"))
      (node (ref "U1") (pin "7") (pinfunction "SCLK_7") (pintype "bidirectional"))
    )
    (net (code "34") (name "Net-(U1-SDIO)") (class "Default")
      (node (ref "R5") (pin "2") (pinfunction "2_2") (pintype "passive"))
      (node (ref "R8") (pin "1") (pinfunction "1_1") (pintype "passive"))
      (node (ref "U1") (pin "8") (pinfunction "SDIO_8") (pintype "bidirectional"))
    )
    (net (code "35") (name "Net-(U1-VA)") (class "Default")
      (node (ref "C1") (pin "1") (pinfunction "1_1") (pintype "passive"))
      (node (ref "C2") (pin "1") (pinfunction "1_1") (pintype "passive"))
      (node (ref "C3") (pin "1") (pinfunction "1_1") (pintype "passive"))
      (node (ref "L02") (pin "2") (pinfunction "2_2") (pintype "passive"))
      (node (ref "R3") (pin "2") (pinfunction "2_2") (pintype "passive"))
      (node (ref "R7") (pin "2") (pinfunction "2_2") (pintype "passive"))
      (node (ref "R8") (pin "2") (pinfunction "2_2") (pintype "passive"))
      (node (ref "U1") (pin "10") (pinfunction "VIO_10") (pintype "bidirectional"))
      (node (ref "U1") (pin "11") (pinfunction "VD_11") (pintype "bidirectional"))
      (node (ref "U1") (pin "16") (pinfunction "VA_16") (pintype "bidirectional"))
    )
    (net (code "36") (name "Net-(U1-~{RST})") (class "Default")
      (node (ref "R2") (pin "2") (pinfunction "2_2") (pintype "passive"))
      (node (ref "R6") (pin "2") (pinfunction "2_2") (pintype "passive"))
      (node (ref "U1") (pin "5") (pinfunction "~{RST}_5") (pintype "bidirectional"))
    )
    (net (code "37") (name "Net-(U1-~{SEN})") (class "Default")
      (node (ref "R3") (pin "1") (pinfunction "1_1") (pintype "passive"))
      (node (ref "U1") (pin "6") (pinfunction "~{SEN}_6") (pintype "bidirectional"))
    )
    (net (code "38") (name "VCC") (class "Default")
      (node (ref "C32") (pin "1") (pinfunction "1_1") (pintype "passive"))
      (node (ref "C33") (pin "1") (pinfunction "1_1") (pintype "passive"))
      (node (ref "C40") (pin "P$1") (pinfunction "P$1_P$1") (pintype "bidirectional"))
      (node (ref "FET1") (pin "2") (pinfunction "SOURCE_2") (pintype "bidirectional"))
      (node (ref "ISP") (pin "2") (pinfunction "2_2") (pintype "passive"))
      (node (ref "L02") (pin "1") (pinfunction "1_1") (pintype "passive"))
      (node (ref "L03") (pin "1") (pinfunction "1_1") (pintype "passive"))
      (node (ref "MCU") (pin "8") (pinfunction "VCC_8") (pintype "bidirectional"))
      (node (ref "R30") (pin "1") (pinfunction "1_1") (pintype "passive"))
      (node (ref "T4") (pin "TP") (pinfunction "TP_TP") (pintype "input"))
      (node (ref "T5") (pin "TP") (pinfunction "TP_TP") (pintype "input"))
    )
    (net (code "39") (name "unconnected-(U1-ROUT-Pad13)") (class "Default")
      (node (ref "U1") (pin "13") (pinfunction "ROUT_13") (pintype "bidirectional"))
    )
  )
)
